# rtcc.net
KiCad netlist of a schematic drawn in EAGLE
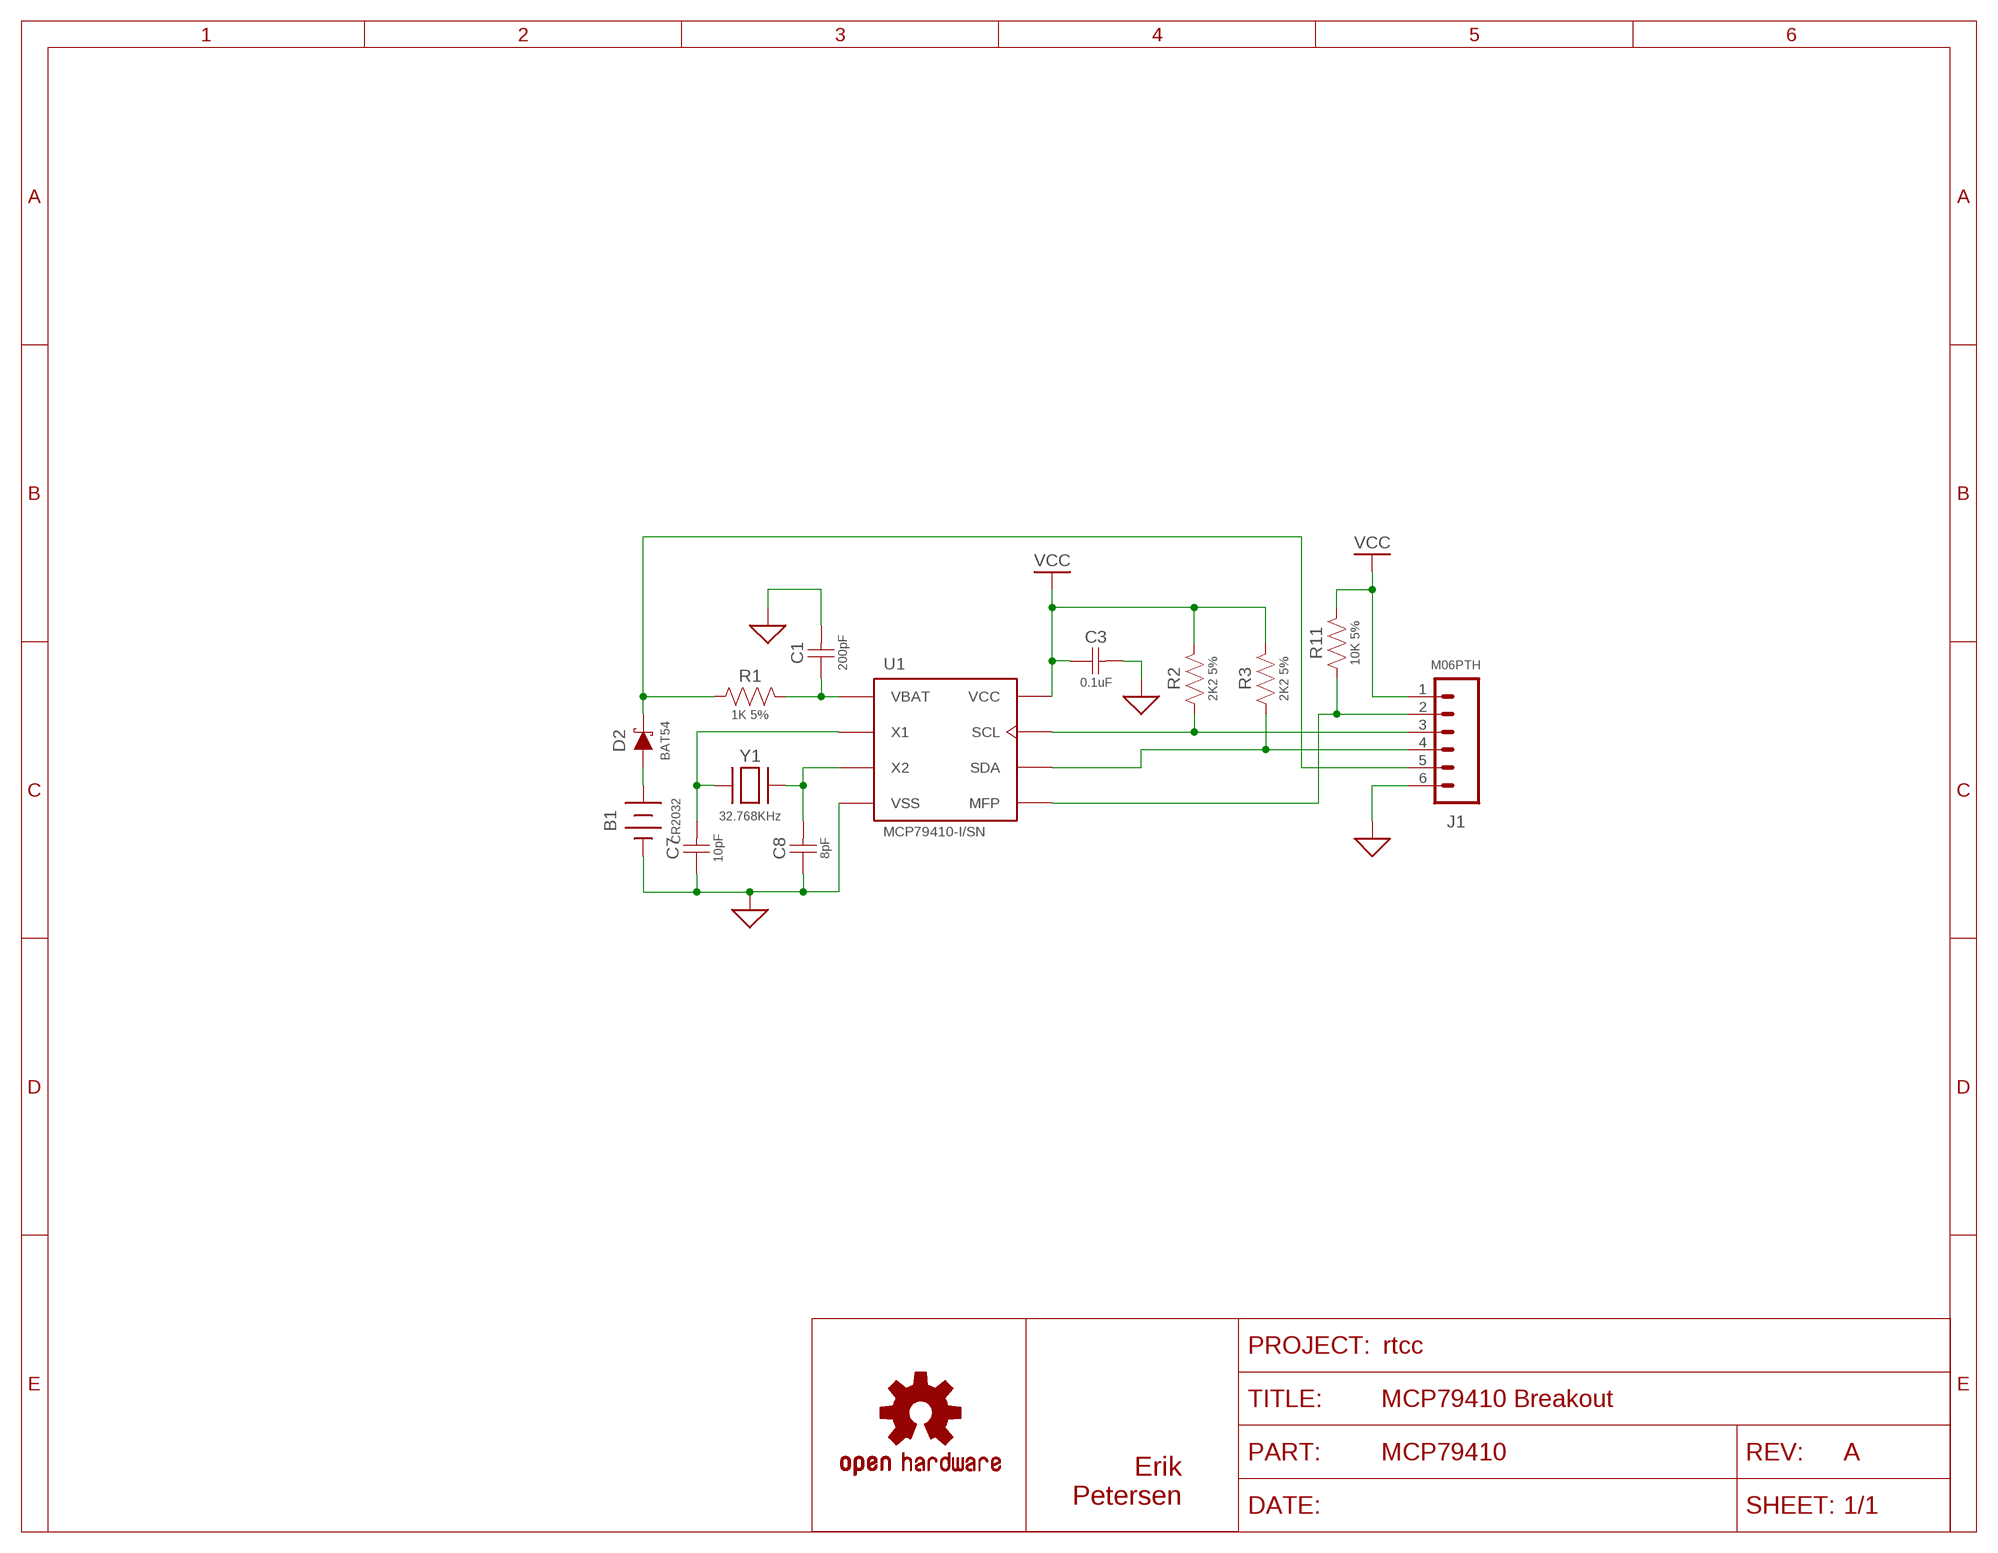
[diagram p0: schematic, sheet 1]

(export (version "E")
  (design (tool "Eeschema 10.0.6"))
  (components
    (comp (ref "B1")
      (value "CR2032")
      (footprint "eagle-import:BK-912")
      (libsource (lib "eagle-import") (part "BK-912"))
    )
    (comp (ref "C1")
      (value "200pF")
      (footprint "eagle-import:18-0603")
      (fields (field (name "TOLERANCE") "±5%") (field (name "VOLTAGE") "50V"))
      (libsource (lib "eagle-import") (part "GRM1885C1H201JA01"))
    )
    (comp (ref "C3")
      (value "0.1uF")
      (footprint "eagle-import:18-0603")
      (fields (field (name "TOLERANCE") "±10%") (field (name "VOLTAGE") "25V"))
      (libsource (lib "eagle-import") (part "GRM188R71E104KA01"))
    )
    (comp (ref "C7")
      (value "10pF")
      (footprint "eagle-import:18-0603_NOSILK")
      (libsource (lib "eagle-import") (part "GRM18NS85C1H100JA01"))
    )
    (comp (ref "C8")
      (value "8pF")
      (footprint "eagle-import:18-0603_NOSILK")
      (libsource (lib "eagle-import") (part "GRM18NS85C1H8R0DZ01"))
    )
    (comp (ref "D2")
      (value "BAT54")
      (footprint "eagle-import:SOT23-3")
      (libsource (lib "eagle-import") (part "BAT54"))
    )
    (comp (ref "J1")
      (value "M06PTH")
      (footprint "eagle-import:1X06")
      (libsource (lib "eagle-import") (part "M06PTH"))
    )
    (comp (ref "LOGO1")
      (value "OSHW-LOGOS")
      (footprint "eagle-import:OSHW-LOGO-S")
      (libsource (lib "eagle-import") (part "OSHW-LOGOS"))
    )
    (comp (ref "R1")
      (value "1K 5%")
      (footprint "eagle-import:R0603")
      (libsource (lib "eagle-import") (part "ERJ-?3GEYJ102"))
    )
    (comp (ref "R2")
      (value "2K2 5%")
      (footprint "eagle-import:R0603")
      (libsource (lib "eagle-import") (part "ERJ-?3GEYJ222"))
    )
    (comp (ref "R3")
      (value "2K2 5%")
      (footprint "eagle-import:R0603")
      (libsource (lib "eagle-import") (part "ERJ-?3GEYJ222"))
    )
    (comp (ref "R11")
      (value "10K 5%")
      (footprint "eagle-import:R0603")
      (libsource (lib "eagle-import") (part "ERJ-?3GEYJ103"))
    )
    (comp (ref "U1")
      (value "MCP79410-I/SN")
      (footprint "eagle-import:SOIC8-N_MC")
      (libsource (lib "eagle-import") (part "MCP794-I/?SN10"))
    )
    (comp (ref "Y1")
      (value "32.768KHz")
      (footprint "eagle-import:4-SOJ")
      (libsource (lib "eagle-import") (part "CM200C32768DZBT"))
    )
  )
  (nets
    (net (code "1") (name "GND") (class "Default")
      (node (ref "B1") (pin "NEG") (pinfunction "GND_NEG") (pintype "power_in"))
      (node (ref "C1") (pin "2") (pinfunction "2_2") (pintype "passive"))
      (node (ref "C3") (pin "2") (pinfunction "2_2") (pintype "passive"))
      (node (ref "C7") (pin "1") (pinfunction "1_1") (pintype "passive"))
      (node (ref "C8") (pin "1") (pinfunction "1_1") (pintype "passive"))
      (node (ref "J1") (pin "6") (pinfunction "6_6") (pintype "passive"))
      (node (ref "U1") (pin "4") (pinfunction "VSS_4") (pintype "passive"))
    )
    (net (code "2") (name "Net-(B1-VBAT-PadPOS1)") (class "Default")
      (node (ref "B1") (pin "POS1") (pinfunction "VBAT_POS1") (pintype "power_in"))
      (node (ref "B1") (pin "POS2") (pinfunction "VBAT_POS2") (pintype "power_in"))
      (node (ref "D2") (pin "A") (pinfunction "A_A") (pintype "passive"))
    )
    (net (code "3") (name "Net-(D2-PadC)") (class "Default")
      (node (ref "D2") (pin "C") (pinfunction "C_C") (pintype "passive"))
      (node (ref "J1") (pin "5") (pinfunction "5_5") (pintype "passive"))
      (node (ref "R1") (pin "1") (pinfunction "1_1") (pintype "passive"))
    )
    (net (code "4") (name "Net-(U1-MFP)") (class "Default")
      (node (ref "J1") (pin "2") (pinfunction "2_2") (pintype "passive"))
      (node (ref "R11") (pin "1") (pinfunction "1_1") (pintype "passive"))
      (node (ref "U1") (pin "7") (pinfunction "MFP_7") (pintype "output"))
    )
    (net (code "5") (name "Net-(U1-SCL)") (class "Default")
      (node (ref "J1") (pin "3") (pinfunction "3_3") (pintype "passive"))
      (node (ref "R2") (pin "1") (pinfunction "1_1") (pintype "passive"))
      (node (ref "U1") (pin "6") (pinfunction "SCL_6") (pintype "input"))
    )
    (net (code "6") (name "Net-(U1-SDA)") (class "Default")
      (node (ref "J1") (pin "4") (pinfunction "4_4") (pintype "passive"))
      (node (ref "R3") (pin "1") (pinfunction "1_1") (pintype "passive"))
      (node (ref "U1") (pin "5") (pinfunction "SDA_5") (pintype "bidirectional"))
    )
    (net (code "7") (name "Net-(U1-VBAT)") (class "Default")
      (node (ref "C1") (pin "1") (pinfunction "1_1") (pintype "passive"))
      (node (ref "R1") (pin "2") (pinfunction "2_2") (pintype "passive"))
      (node (ref "U1") (pin "3") (pinfunction "VBAT_3") (pintype "passive"))
    )
    (net (code "8") (name "Net-(U1-X1)") (class "Default")
      (node (ref "C7") (pin "2") (pinfunction "2_2") (pintype "passive"))
      (node (ref "U1") (pin "1") (pinfunction "X1_1") (pintype "bidirectional"))
      (node (ref "Y1") (pin "1") (pinfunction "A_1") (pintype "passive"))
    )
    (net (code "9") (name "Net-(U1-X2)") (class "Default")
      (node (ref "C8") (pin "2") (pinfunction "2_2") (pintype "passive"))
      (node (ref "U1") (pin "2") (pinfunction "X2_2") (pintype "bidirectional"))
      (node (ref "Y1") (pin "4") (pinfunction "B_4") (pintype "passive"))
    )
    (net (code "10") (name "VCC") (class "Default")
      (node (ref "C3") (pin "1") (pinfunction "1_1") (pintype "passive"))
      (node (ref "J1") (pin "1") (pinfunction "1_1") (pintype "passive"))
      (node (ref "R11") (pin "2") (pinfunction "2_2") (pintype "passive"))
      (node (ref "R2") (pin "2") (pinfunction "2_2") (pintype "passive"))
      (node (ref "R3") (pin "2") (pinfunction "2_2") (pintype "passive"))
      (node (ref "U1") (pin "8") (pinfunction "VCC_8") (pintype "power_in"))
    )
  )
)
